# neopixelDriverBoard.net
KiCad netlist of a schematic drawn in EAGLE
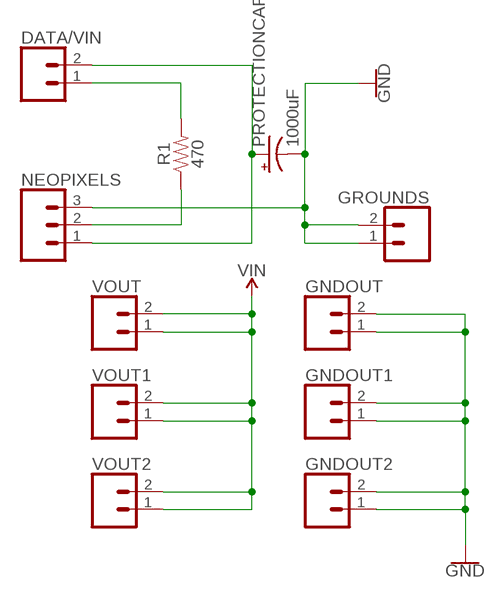
[diagram p0: schematic, sheet 1]

(export (version "E")
  (design (tool "Eeschema 10.0.6"))
  (components
    (comp (ref "DATA/VIN")
      (value "CONN_025MM")
      (footprint "eagle-import:SCREWTERMINAL-5MM-2")
      (libsource (lib "eagle-import") (part "CONN_025MM"))
    )
    (comp (ref "GNDOUT")
      (value "CONN_025MM")
      (footprint "eagle-import:SCREWTERMINAL-5MM-2")
      (libsource (lib "eagle-import") (part "CONN_025MM"))
    )
    (comp (ref "GNDOUT1")
      (value "CONN_025MM")
      (footprint "eagle-import:SCREWTERMINAL-5MM-2")
      (libsource (lib "eagle-import") (part "CONN_025MM"))
    )
    (comp (ref "GNDOUT2")
      (value "CONN_025MM")
      (footprint "eagle-import:SCREWTERMINAL-5MM-2")
      (libsource (lib "eagle-import") (part "CONN_025MM"))
    )
    (comp (ref "GROUNDS")
      (value "CONN_025MM")
      (footprint "eagle-import:SCREWTERMINAL-5MM-2")
      (libsource (lib "eagle-import") (part "CONN_025MM"))
    )
    (comp (ref "NEOPIXELS")
      (value "CONN_03-SCREW-5MM")
      (footprint "eagle-import:SCREWTERMINAL-5MM-3")
      (libsource (lib "eagle-import") (part "CONN_03-SCREW-5MM"))
    )
    (comp (ref "PROTECTIONCAP")
      (value "1000uF")
      (footprint "eagle-import:CPOL-RADIAL-5MM-10MM")
      (libsource (lib "eagle-import") (part "1000UF-RADIAL-5MM-25V-20%"))
    )
    (comp (ref "R1")
      (value "470")
      (footprint "eagle-import:AXIAL-0.3-KIT")
      (libsource (lib "eagle-import") (part "1KOHM-HORIZ_KIT-1/4W-1%"))
    )
    (comp (ref "VOUT")
      (value "CONN_025MM")
      (footprint "eagle-import:SCREWTERMINAL-5MM-2")
      (libsource (lib "eagle-import") (part "CONN_025MM"))
    )
    (comp (ref "VOUT1")
      (value "CONN_025MM")
      (footprint "eagle-import:SCREWTERMINAL-5MM-2")
      (libsource (lib "eagle-import") (part "CONN_025MM"))
    )
    (comp (ref "VOUT2")
      (value "CONN_025MM")
      (footprint "eagle-import:SCREWTERMINAL-5MM-2")
      (libsource (lib "eagle-import") (part "CONN_025MM"))
    )
  )
  (nets
    (net (code "1") (name "GND") (class "Default")
      (node (ref "GNDOUT") (pin "1") (pinfunction "1_1") (pintype "passive"))
      (node (ref "GNDOUT") (pin "2") (pinfunction "2_2") (pintype "passive"))
      (node (ref "GNDOUT1") (pin "1") (pinfunction "1_1") (pintype "passive"))
      (node (ref "GNDOUT1") (pin "2") (pinfunction "2_2") (pintype "passive"))
      (node (ref "GNDOUT2") (pin "1") (pinfunction "1_1") (pintype "passive"))
      (node (ref "GNDOUT2") (pin "2") (pinfunction "2_2") (pintype "passive"))
      (node (ref "GROUNDS") (pin "1") (pinfunction "1_1") (pintype "passive"))
      (node (ref "GROUNDS") (pin "2") (pinfunction "2_2") (pintype "passive"))
      (node (ref "NEOPIXELS") (pin "3") (pinfunction "3_3") (pintype "passive"))
      (node (ref "PROTECTIONCAP") (pin "-") (pinfunction "-_-") (pintype "passive"))
    )
    (net (code "2") (name "Net-(R1-1)") (class "Default")
      (node (ref "NEOPIXELS") (pin "2") (pinfunction "2_2") (pintype "passive"))
      (node (ref "R1") (pin "P$1") (pinfunction "1_P$1") (pintype "passive"))
    )
    (net (code "3") (name "Net-(R1-2)") (class "Default")
      (node (ref "DATA/VIN") (pin "1") (pinfunction "1_1") (pintype "passive"))
      (node (ref "R1") (pin "P$2") (pinfunction "2_P$2") (pintype "passive"))
    )
    (net (code "4") (name "VIN") (class "Default")
      (node (ref "DATA/VIN") (pin "2") (pinfunction "2_2") (pintype "passive"))
      (node (ref "NEOPIXELS") (pin "1") (pinfunction "1_1") (pintype "passive"))
      (node (ref "PROTECTIONCAP") (pin "+") (pinfunction "+_+") (pintype "passive"))
      (node (ref "VOUT") (pin "1") (pinfunction "1_1") (pintype "passive"))
      (node (ref "VOUT") (pin "2") (pinfunction "2_2") (pintype "passive"))
      (node (ref "VOUT1") (pin "1") (pinfunction "1_1") (pintype "passive"))
      (node (ref "VOUT1") (pin "2") (pinfunction "2_2") (pintype "passive"))
      (node (ref "VOUT2") (pin "1") (pinfunction "1_1") (pintype "passive"))
      (node (ref "VOUT2") (pin "2") (pinfunction "2_2") (pintype "passive"))
    )
  )
)
